# Clock_Extension.net
KiCad netlist of a schematic drawn in EAGLE
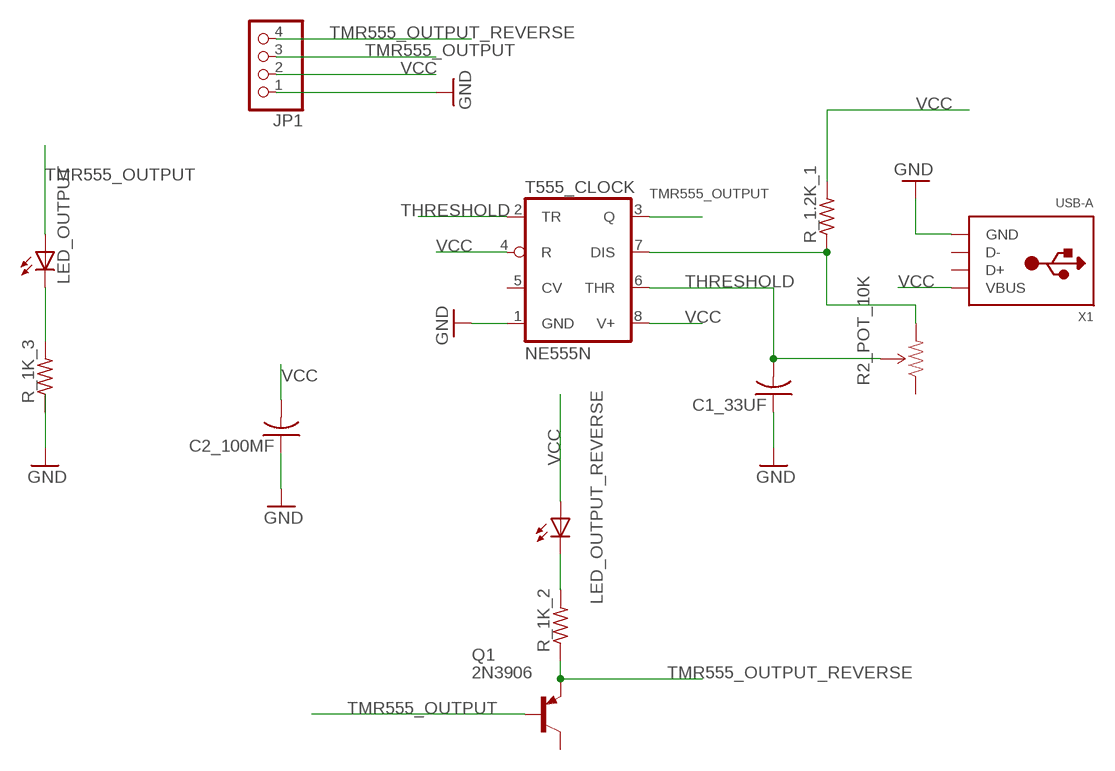
[diagram p0: schematic, sheet 1]

(export (version "E")
  (design (tool "Eeschema 10.0.6"))
  (components
    (comp (ref "C1_33UF")
      (value "C-US025-030X050")
      (footprint "eagle-import:C025-030X050")
      (libsource (lib "eagle-import") (part "C-US025-030X050"))
    )
    (comp (ref "C2_100MF")
      (value "C-US025-030X050")
      (footprint "eagle-import:C025-030X050")
      (libsource (lib "eagle-import") (part "C-US025-030X050"))
    )
    (comp (ref "JP1")
      (value "PINHD-1X4")
      (footprint "eagle-import:1X04")
      (libsource (lib "eagle-import") (part "PINHD-1X4"))
    )
    (comp (ref "LED_OUTPUT")
      (value "LEDSMT1206")
      (footprint "eagle-import:1206")
      (libsource (lib "eagle-import") (part "LEDSMT1206"))
    )
    (comp (ref "LED_OUTPUT_REVERSE")
      (value "LEDSMT1206")
      (footprint "eagle-import:1206")
      (libsource (lib "eagle-import") (part "LEDSMT1206"))
    )
    (comp (ref "Q1")
      (value "2N3906")
      (footprint "eagle-import:TO92")
      (libsource (lib "eagle-import") (part "2N3906"))
    )
    (comp (ref "R2_POT_10K")
      (value "TRIMPOTPTH")
      (footprint "eagle-import:TRIM_POT_PTH")
      (libsource (lib "eagle-import") (part "TRIMPOTPTH"))
    )
    (comp (ref "R_1.2K_1")
      (value "R-US_R1206")
      (footprint "eagle-import:R1206")
      (libsource (lib "eagle-import") (part "R-US_R1206"))
    )
    (comp (ref "R_1K_2")
      (value "R-US_R1206")
      (footprint "eagle-import:R1206")
      (libsource (lib "eagle-import") (part "R-US_R1206"))
    )
    (comp (ref "R_1K_3")
      (value "R-US_R1206")
      (footprint "eagle-import:R1206")
      (libsource (lib "eagle-import") (part "R-US_R1206"))
    )
    (comp (ref "T555_CLOCK")
      (value "NE555N")
      (footprint "eagle-import:DIL08")
      (libsource (lib "eagle-import") (part "555NNE"))
    )
    (comp (ref "X1")
      (value "USB-A")
      (footprint "eagle-import:MOLEX_480371000")
      (libsource (lib "eagle-import") (part "USB-A"))
    )
  )
  (nets
    (net (code "1") (name "/THRESHOLD") (class "Default")
      (node (ref "C1_33UF") (pin "2") (pinfunction "2_2") (pintype "passive"))
      (node (ref "R2_POT_10K") (pin "2") (pinfunction "WIPER_2") (pintype "passive"))
      (node (ref "T555_CLOCK") (pin "2") (pinfunction "TR_2") (pintype "input"))
      (node (ref "T555_CLOCK") (pin "6") (pinfunction "THR_6") (pintype "input"))
    )
    (net (code "2") (name "/TMR555_OUTPUT") (class "Default")
      (node (ref "JP1") (pin "3") (pinfunction "3_3") (pintype "passive"))
      (node (ref "LED_OUTPUT") (pin "A") (pinfunction "A_A") (pintype "passive"))
      (node (ref "Q1") (pin "2") (pinfunction "B_2") (pintype "passive"))
      (node (ref "T555_CLOCK") (pin "3") (pinfunction "Q_3") (pintype "output"))
    )
    (net (code "3") (name "/TMR555_OUTPUT_REVERSE") (class "Default")
      (node (ref "JP1") (pin "4") (pinfunction "4_4") (pintype "passive"))
      (node (ref "Q1") (pin "3") (pinfunction "E_3") (pintype "passive"))
      (node (ref "R_1K_2") (pin "1") (pinfunction "1_1") (pintype "passive"))
    )
    (net (code "4") (name "/VCC") (class "Default")
      (node (ref "C2_100MF") (pin "2") (pinfunction "2_2") (pintype "passive"))
      (node (ref "JP1") (pin "2") (pinfunction "2_2") (pintype "passive"))
      (node (ref "LED_OUTPUT_REVERSE") (pin "A") (pinfunction "A_A") (pintype "passive"))
      (node (ref "R_1.2K_1") (pin "2") (pinfunction "2_2") (pintype "passive"))
      (node (ref "T555_CLOCK") (pin "4") (pinfunction "R_4") (pintype "input"))
      (node (ref "T555_CLOCK") (pin "8") (pinfunction "V+_8") (pintype "power_in"))
      (node (ref "X1") (pin "1") (pinfunction "VBUS_1") (pintype "power_in"))
    )
    (net (code "5") (name "GND") (class "Default")
      (node (ref "C1_33UF") (pin "1") (pinfunction "1_1") (pintype "passive"))
      (node (ref "C2_100MF") (pin "1") (pinfunction "1_1") (pintype "passive"))
      (node (ref "JP1") (pin "1") (pinfunction "1_1") (pintype "passive"))
      (node (ref "R_1K_3") (pin "1") (pinfunction "1_1") (pintype "passive"))
      (node (ref "T555_CLOCK") (pin "1") (pinfunction "GND_1") (pintype "power_in"))
      (node (ref "X1") (pin "4") (pinfunction "GND_4") (pintype "power_in"))
    )
    (net (code "6") (name "Net-(LED_OUTPUT-PadC)") (class "Default")
      (node (ref "LED_OUTPUT") (pin "C") (pinfunction "C_C") (pintype "passive"))
      (node (ref "R_1K_3") (pin "2") (pinfunction "2_2") (pintype "passive"))
    )
    (net (code "7") (name "Net-(LED_OUTPUT_REVERSE-PadC)") (class "Default")
      (node (ref "LED_OUTPUT_REVERSE") (pin "C") (pinfunction "C_C") (pintype "passive"))
      (node (ref "R_1K_2") (pin "2") (pinfunction "2_2") (pintype "passive"))
    )
    (net (code "8") (name "Net-(R2_POT_10K-CW)") (class "Default")
      (node (ref "R2_POT_10K") (pin "3") (pinfunction "CW_3") (pintype "passive"))
      (node (ref "R_1.2K_1") (pin "1") (pinfunction "1_1") (pintype "passive"))
      (node (ref "T555_CLOCK") (pin "7") (pinfunction "DIS_7") (pintype "input"))
    )
    (net (code "9") (name "unconnected-(Q1-C-Pad1)") (class "Default")
      (node (ref "Q1") (pin "1") (pinfunction "C_1") (pintype "passive"))
    )
    (net (code "10") (name "unconnected-(R2_POT_10K-CCW-Pad1)") (class "Default")
      (node (ref "R2_POT_10K") (pin "1") (pinfunction "CCW_1") (pintype "passive"))
    )
    (net (code "11") (name "unconnected-(T555_CLOCK-CV-Pad5)") (class "Default")
      (node (ref "T555_CLOCK") (pin "5") (pinfunction "CV_5") (pintype "input"))
    )
    (net (code "12") (name "unconnected-(X1-D+-Pad3)") (class "Default")
      (node (ref "X1") (pin "3") (pinfunction "D+_3") (pintype "bidirectional"))
    )
    (net (code "13") (name "unconnected-(X1-D--Pad2)") (class "Default")
      (node (ref "X1") (pin "2") (pinfunction "D-_2") (pintype "bidirectional"))
    )
  )
)
